# VOLTAGE_REGULATOR.net
KiCad netlist of a schematic drawn in Altium Designer
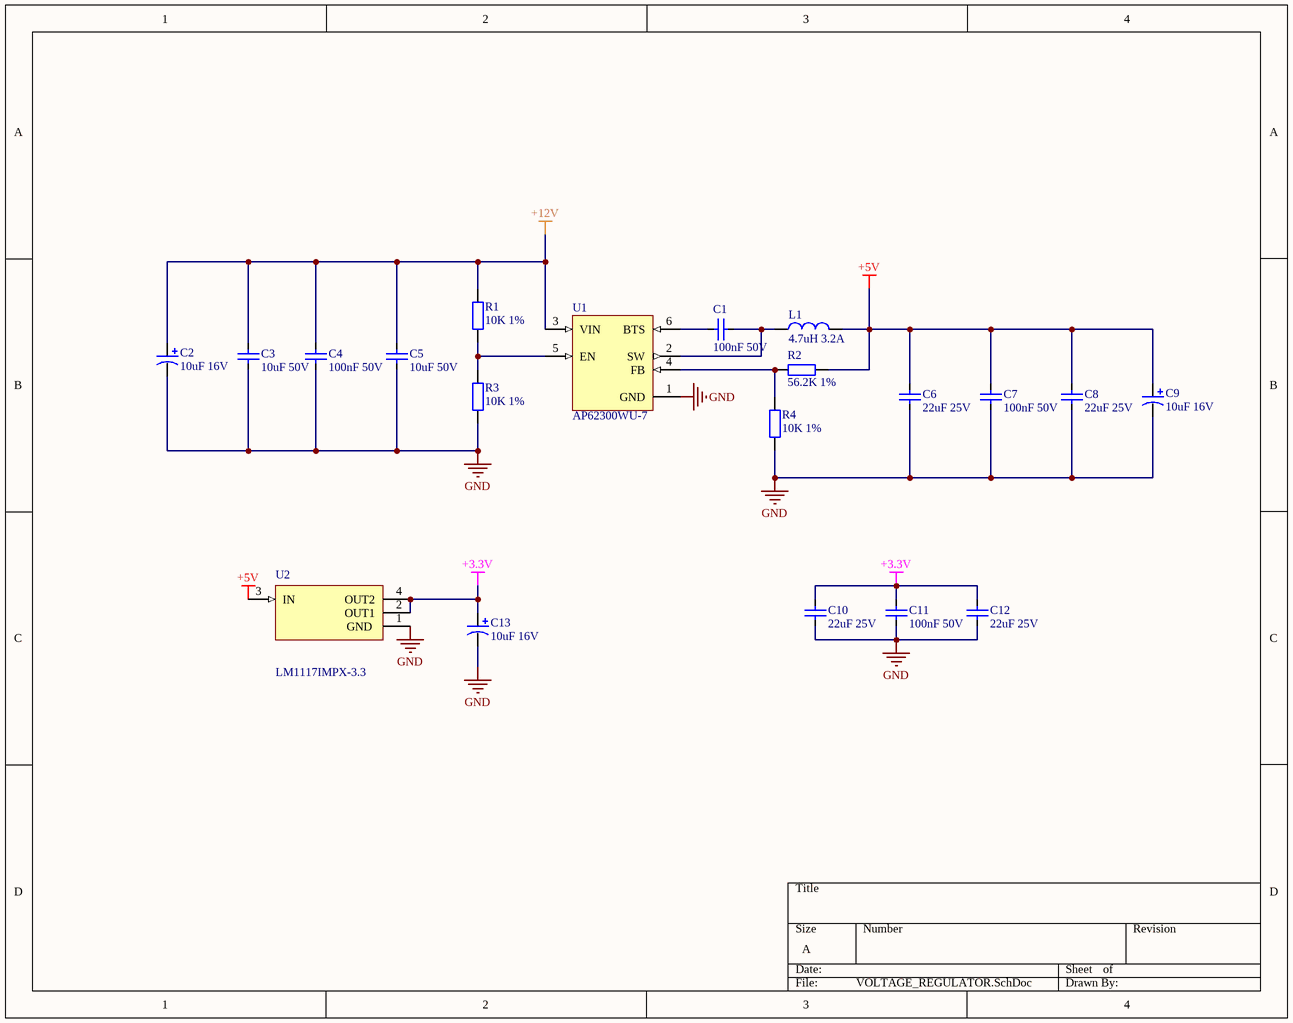
[diagram p0: VOLTAGE_REGULATOR.SchDoc]

(export (version "E")
  (design (tool "Eeschema 10.0.6"))
  (components
    (comp (ref "C1")
      (value "100nF 50V")
      (footprint "CAP_SMD_0805")
      (description "0.1 µF ±10% 50V Ceramic Capacitor X7R 0805 (2012 Metric)")
      (fields
        (field (name "MANUFACTURER") "YAGEO")
        (field (name "MANUFACTURE PART NUMBER") "CC0805KRX7R9BB104")
      )
      (libsource (lib "Nhatkhongbuon") (part "C0805_MLCC_100nF_50V"))
    )
    (comp (ref "C2")
      (value "10uF 16V")
      (footprint "CAP-ALU-SMD-C")
      (description "10 µF 16 V Aluminum - Polymer Capacitors Radial, Can - SMD 30mOhm 2000 Hrs @ 105°C")
      (fields
        (field (name "MANUFACTURER") "Würth Elektronik")
        (field (name "MANUFACTURE PART NUMBER") "875105359001")
      )
      (libsource (lib "Nhatkhongbuon") (part "C_ALU_10uF_16V"))
    )
    (comp (ref "C3")
      (value "10uF 50V")
      (footprint "CAP_SMD_0805")
      (description "10 µF ±20% 50V Ceramic Capacitor X5R 0805 (2012 Metric)")
      (fields
        (field (name "MANUFACTURER") "Murata Electronics")
        (field (name "MANUFACTURE PART NUMBER") "GRM21BR61H106ME43L")
      )
      (libsource (lib "Nhatkhongbuon") (part "C0805_MLCC_10uF_50V"))
    )
    (comp (ref "C4")
      (value "100nF 50V")
      (footprint "CAP_SMD_0805")
      (description "0.1 µF ±10% 50V Ceramic Capacitor X7R 0805 (2012 Metric)")
      (fields
        (field (name "MANUFACTURER") "YAGEO")
        (field (name "MANUFACTURE PART NUMBER") "CC0805KRX7R9BB104")
      )
      (libsource (lib "Nhatkhongbuon") (part "C0805_MLCC_100nF_50V"))
    )
    (comp (ref "C5")
      (value "10uF 50V")
      (footprint "CAP_SMD_0805")
      (description "10 µF ±20% 50V Ceramic Capacitor X5R 0805 (2012 Metric)")
      (fields
        (field (name "MANUFACTURER") "Murata Electronics")
        (field (name "MANUFACTURE PART NUMBER") "GRM21BR61H106ME43L")
      )
      (libsource (lib "Nhatkhongbuon") (part "C0805_MLCC_10uF_50V"))
    )
    (comp (ref "C6")
      (value "22uF 25V")
      (footprint "CAP_SMD_0805")
      (description "22 µF ±20% 25V Ceramic Capacitor X5R 0805 (2012 Metric)")
      (fields
        (field (name "MANUFACTURER") "Samsung Electro-Mechanics")
        (field (name "MANUFACTURE PART NUMBER") "CL21A226MAYNNNE")
      )
      (libsource (lib "Nhatkhongbuon") (part "C0805_MLCC_22uF_25V"))
    )
    (comp (ref "C7")
      (value "100nF 50V")
      (footprint "CAP_SMD_0805")
      (description "0.1 µF ±10% 50V Ceramic Capacitor X7R 0805 (2012 Metric)")
      (fields
        (field (name "MANUFACTURER") "YAGEO")
        (field (name "MANUFACTURE PART NUMBER") "CC0805KRX7R9BB104")
      )
      (libsource (lib "Nhatkhongbuon") (part "C0805_MLCC_100nF_50V"))
    )
    (comp (ref "C8")
      (value "22uF 25V")
      (footprint "CAP_SMD_0805")
      (description "22 µF ±20% 25V Ceramic Capacitor X5R 0805 (2012 Metric)")
      (fields
        (field (name "MANUFACTURER") "Samsung Electro-Mechanics")
        (field (name "MANUFACTURE PART NUMBER") "CL21A226MAYNNNE")
      )
      (libsource (lib "Nhatkhongbuon") (part "C0805_MLCC_22uF_25V"))
    )
    (comp (ref "C9")
      (value "10uF 16V")
      (footprint "CAP-ALU-SMD-C")
      (description "10 µF 16 V Aluminum - Polymer Capacitors Radial, Can - SMD 30mOhm 2000 Hrs @ 105°C")
      (fields
        (field (name "MANUFACTURER") "Würth Elektronik")
        (field (name "MANUFACTURE PART NUMBER") "875105359001")
      )
      (libsource (lib "Nhatkhongbuon") (part "C_ALU_10uF_16V"))
    )
    (comp (ref "C10")
      (value "22uF 25V")
      (footprint "CAP_SMD_0805")
      (description "22 µF ±20% 25V Ceramic Capacitor X5R 0805 (2012 Metric)")
      (fields
        (field (name "MANUFACTURER") "Samsung Electro-Mechanics")
        (field (name "MANUFACTURE PART NUMBER") "CL21A226MAYNNNE")
      )
      (libsource (lib "Nhatkhongbuon") (part "C0805_MLCC_22uF_25V"))
    )
    (comp (ref "C11")
      (value "100nF 50V")
      (footprint "CAP_SMD_0805")
      (description "0.1 µF ±10% 50V Ceramic Capacitor X7R 0805 (2012 Metric)")
      (fields
        (field (name "MANUFACTURER") "YAGEO")
        (field (name "MANUFACTURE PART NUMBER") "CC0805KRX7R9BB104")
      )
      (libsource (lib "Nhatkhongbuon") (part "C0805_MLCC_100nF_50V"))
    )
    (comp (ref "C12")
      (value "22uF 25V")
      (footprint "CAP_SMD_0805")
      (description "22 µF ±20% 25V Ceramic Capacitor X5R 0805 (2012 Metric)")
      (fields
        (field (name "MANUFACTURER") "Samsung Electro-Mechanics")
        (field (name "MANUFACTURE PART NUMBER") "CL21A226MAYNNNE")
      )
      (libsource (lib "Nhatkhongbuon") (part "C0805_MLCC_22uF_25V"))
    )
    (comp (ref "C13")
      (value "10uF 16V")
      (footprint "CAP-ALU-SMD-C")
      (description "10 µF 16 V Aluminum - Polymer Capacitors Radial, Can - SMD 30mOhm 2000 Hrs @ 105°C")
      (fields
        (field (name "MANUFACTURER") "Würth Elektronik")
        (field (name "MANUFACTURE PART NUMBER") "875105359001")
      )
      (libsource (lib "Nhatkhongbuon") (part "C_ALU_10uF_16V"))
    )
    (comp (ref "L1")
      (value "4.7uH 3.2A")
      (footprint "L_5.5X5.2")
      (description "4.7 µH Shielded Molded Inductor 3.2 A 81.3mOhm Max Nonstandard")
      (fields
        (field (name "MANUFACTURER") "Vishay Dale")
        (field (name "MANUFACTURE PART NUMBER") "IHLP2020BZER4R7M11")
      )
      (libsource (lib "Nhatkhongbuon") (part "L_SMD_4.7uH_3.2A"))
    )
    (comp (ref "R1")
      (value "10K 1%")
      (footprint "RES_SMD_0805")
      (description "10 kOhms ±1% 0.125W, 1/8W Chip Resistor 0805 (2012 Metric) Moisture Resistant Thick Film")
      (fields
        (field (name "MANUFACTURER") "YAGEO")
        (field (name "MANUFACTURE PART NUMBER") "RC0805FR-0710KL")
      )
      (libsource (lib "Nhatkhongbuon") (part "R0805_10K"))
    )
    (comp (ref "R2")
      (value "56.2K 1%")
      (footprint "RES_SMD_0805")
      (description "56.2 kOhms ±1% 0.125W, 1/8W Chip Resistor 0805 (2012 Metric) Moisture Resistant Thick Film")
      (fields
        (field (name "MANUFACTURER") "YAGEO")
        (field (name "MANUFACTURE PART NUMBER") "RC0805FR-0756K2L")
      )
      (libsource (lib "Nhatkhongbuon") (part "R0805_56.2K"))
    )
    (comp (ref "R3")
      (value "10K 1%")
      (footprint "RES_SMD_0805")
      (description "10 kOhms ±1% 0.125W, 1/8W Chip Resistor 0805 (2012 Metric) Moisture Resistant Thick Film")
      (fields
        (field (name "MANUFACTURER") "YAGEO")
        (field (name "MANUFACTURE PART NUMBER") "RC0805FR-0710KL")
      )
      (libsource (lib "Nhatkhongbuon") (part "R0805_10K"))
    )
    (comp (ref "R4")
      (value "10K 1%")
      (footprint "RES_SMD_0805")
      (description "10 kOhms ±1% 0.125W, 1/8W Chip Resistor 0805 (2012 Metric) Moisture Resistant Thick Film")
      (fields
        (field (name "MANUFACTURER") "YAGEO")
        (field (name "MANUFACTURE PART NUMBER") "RC0805FR-0710KL")
      )
      (libsource (lib "Nhatkhongbuon") (part "R0805_10K"))
    )
    (comp (ref "U1")
      (value "AP62300WU-7")
      (footprint "SOT-23-6")
      (description "Buck Switching Regulator IC Positive Adjustable 0.8V 1 Output 3A SOT-23-6 Thin, TSOT-23-6")
      (fields (field (name "MANUFACTURER") "Diodes Incorporated"))
      (libsource (lib "Nhatkhongbuon") (part "AP62300WU-7"))
    )
    (comp (ref "U2")
      (value "LM1117IMPX-3.3")
      (footprint "SOT-223-4")
      (description "Linear Voltage Regulator IC Positive Fixed 1 Output 800mA SOT-223-4")
      (fields
        (field (name "MANUFACTURER") "Texas Instruments")
        (field (name "MANUFACTURE PART NUMBER") "LM1117IMPX-3.3/NOPB")
      )
      (libsource (lib "Nhatkhongbuon") (part "LM1117IMPX-3.3/NOPB"))
    )
  )
  (nets
    (net (code "1") (name "+3.3V") (class "Default")
      (node (ref "C10") (pin "2") (pinfunction "2_2") (pintype "passive"))
      (node (ref "C11") (pin "2") (pinfunction "2_2") (pintype "passive"))
      (node (ref "C12") (pin "2") (pinfunction "2_2") (pintype "passive"))
      (node (ref "C13") (pin "1") (pinfunction "1_1") (pintype "passive"))
      (node (ref "U2") (pin "2") (pinfunction "OUT1_2") (pintype "power_in"))
      (node (ref "U2") (pin "4") (pinfunction "OUT2_4") (pintype "power_in"))
    )
    (net (code "2") (name "+5V") (class "Default")
      (node (ref "C6") (pin "2") (pinfunction "2_2") (pintype "passive"))
      (node (ref "C7") (pin "2") (pinfunction "2_2") (pintype "passive"))
      (node (ref "C8") (pin "2") (pinfunction "2_2") (pintype "passive"))
      (node (ref "C9") (pin "1") (pinfunction "1_1") (pintype "passive"))
      (node (ref "L1") (pin "2") (pinfunction "2_2") (pintype "passive"))
      (node (ref "R2") (pin "2") (pinfunction "2_2") (pintype "passive"))
      (node (ref "U2") (pin "3") (pinfunction "IN_3") (pintype "input"))
    )
    (net (code "3") (name "+12V") (class "Default")
      (node (ref "C2") (pin "1") (pinfunction "1_1") (pintype "passive"))
      (node (ref "C3") (pin "2") (pinfunction "2_2") (pintype "passive"))
      (node (ref "C4") (pin "2") (pinfunction "2_2") (pintype "passive"))
      (node (ref "C5") (pin "2") (pinfunction "2_2") (pintype "passive"))
      (node (ref "R1") (pin "2") (pinfunction "2_2") (pintype "passive"))
      (node (ref "U1") (pin "3") (pinfunction "VIN_3") (pintype "input"))
    )
    (net (code "4") (name "GND") (class "Default")
      (node (ref "C10") (pin "1") (pinfunction "1_1") (pintype "passive"))
      (node (ref "C11") (pin "1") (pinfunction "1_1") (pintype "passive"))
      (node (ref "C12") (pin "1") (pinfunction "1_1") (pintype "passive"))
      (node (ref "C13") (pin "2") (pinfunction "2_2") (pintype "passive"))
      (node (ref "C2") (pin "2") (pinfunction "2_2") (pintype "passive"))
      (node (ref "C3") (pin "1") (pinfunction "1_1") (pintype "passive"))
      (node (ref "C4") (pin "1") (pinfunction "1_1") (pintype "passive"))
      (node (ref "C5") (pin "1") (pinfunction "1_1") (pintype "passive"))
      (node (ref "C6") (pin "1") (pinfunction "1_1") (pintype "passive"))
      (node (ref "C7") (pin "1") (pinfunction "1_1") (pintype "passive"))
      (node (ref "C8") (pin "1") (pinfunction "1_1") (pintype "passive"))
      (node (ref "C9") (pin "2") (pinfunction "2_2") (pintype "passive"))
      (node (ref "R3") (pin "1") (pinfunction "1_1") (pintype "passive"))
      (node (ref "R4") (pin "1") (pinfunction "1_1") (pintype "passive"))
      (node (ref "U1") (pin "1") (pinfunction "GND_1") (pintype "passive"))
      (node (ref "U2") (pin "1") (pinfunction "GND_1") (pintype "passive"))
    )
    (net (code "5") (name "Net-(U1-BTS)") (class "Default")
      (node (ref "C1") (pin "2") (pinfunction "2_2") (pintype "passive"))
      (node (ref "U1") (pin "6") (pinfunction "BTS_6") (pintype "input"))
    )
    (net (code "6") (name "Net-(U1-EN)") (class "Default")
      (node (ref "R1") (pin "1") (pinfunction "1_1") (pintype "passive"))
      (node (ref "R3") (pin "2") (pinfunction "2_2") (pintype "passive"))
      (node (ref "U1") (pin "5") (pinfunction "EN_5") (pintype "input"))
    )
    (net (code "7") (name "Net-(U1-FB)") (class "Default")
      (node (ref "R2") (pin "1") (pinfunction "1_1") (pintype "passive"))
      (node (ref "R4") (pin "2") (pinfunction "2_2") (pintype "passive"))
      (node (ref "U1") (pin "4") (pinfunction "FB_4") (pintype "input"))
    )
    (net (code "8") (name "Net-(U1-SW)") (class "Default")
      (node (ref "C1") (pin "1") (pinfunction "1_1") (pintype "passive"))
      (node (ref "L1") (pin "1") (pinfunction "1_1") (pintype "passive"))
      (node (ref "U1") (pin "2") (pinfunction "SW_2") (pintype "output"))
    )
  )
)
